# BBB_Headers.net
KiCad netlist of a schematic drawn in Altium Designer
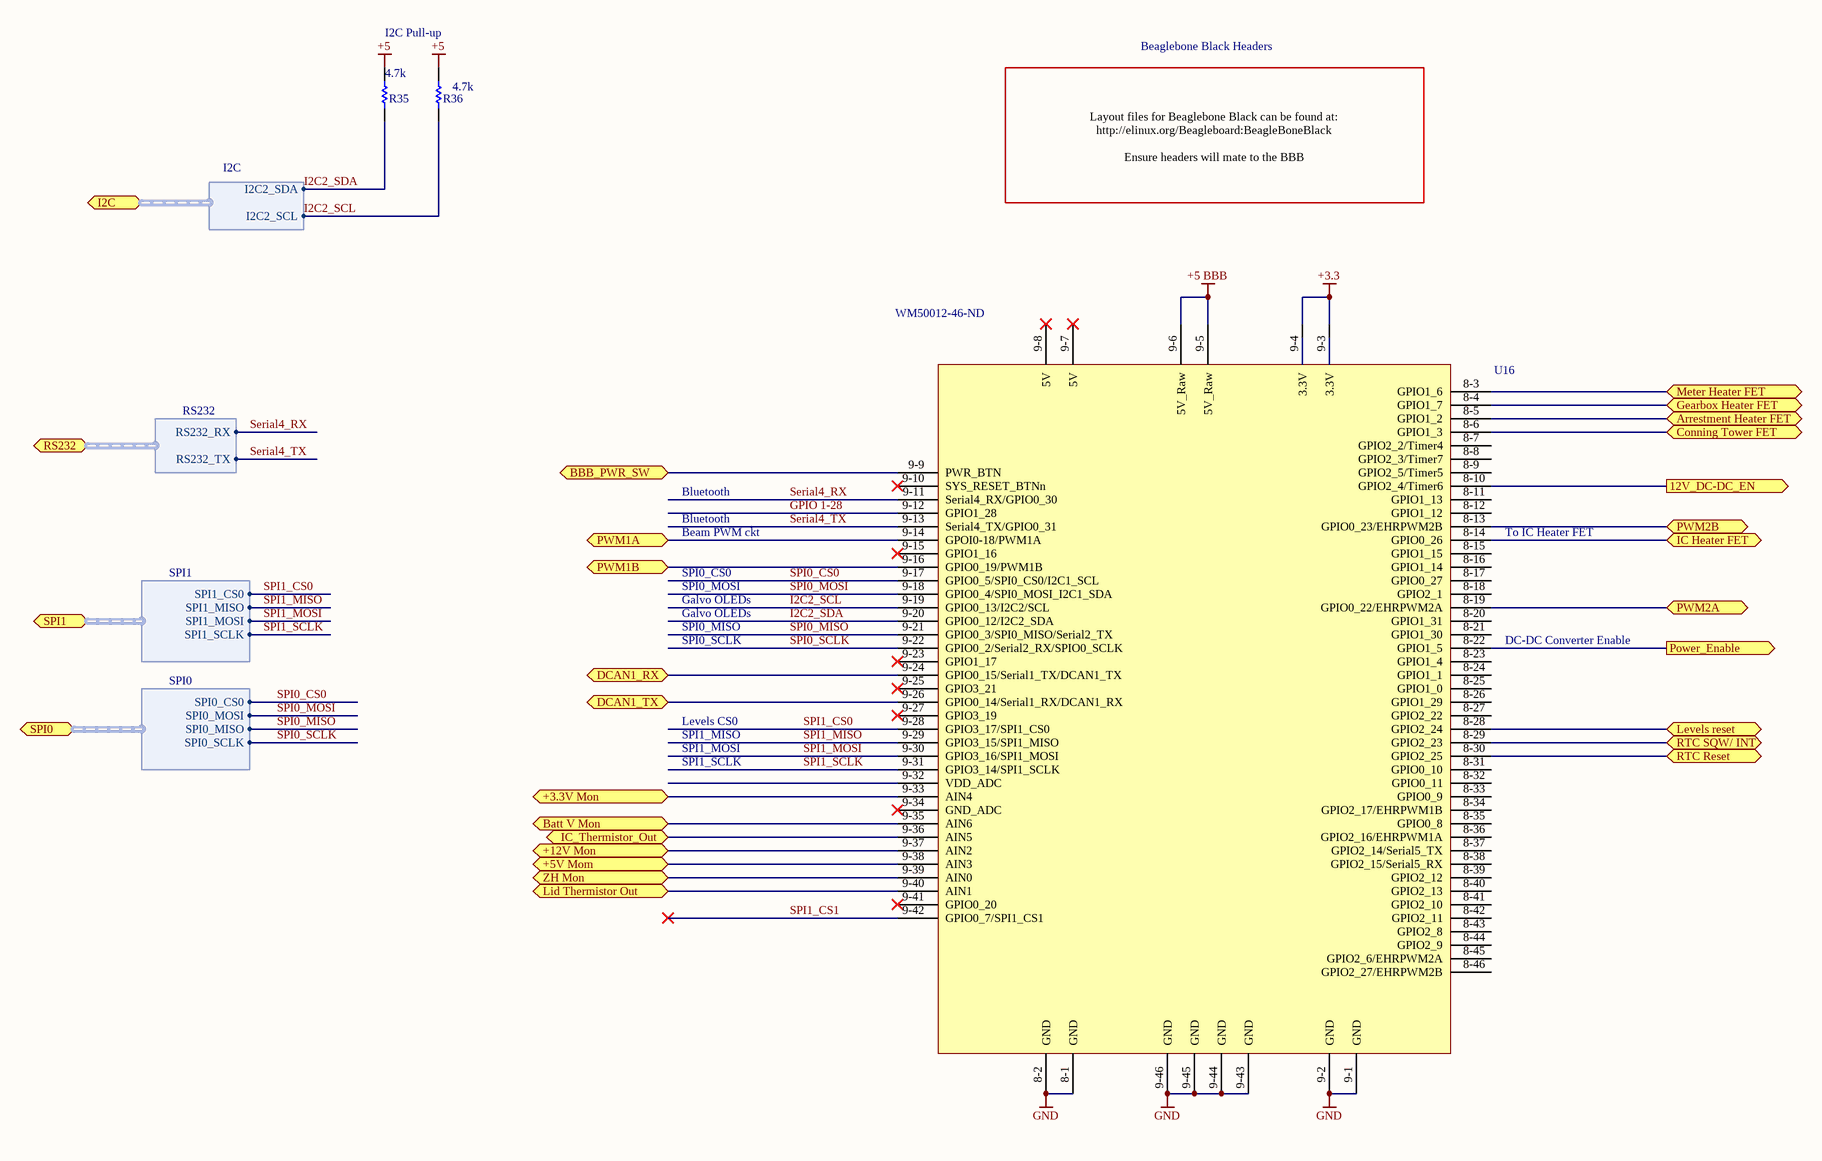
[diagram p0: BBB Headers.SchDoc]

(export (version "E")
  (design (tool "Eeschema 10.0.6"))
  (components
    (comp (ref "R35")
      (value "3K74 0.125W 1% 0805 (2012 Metric)  SMD")
      (footprint "RESC0805(2012)_N")
      (fields
        (field (name "MANUFACTURER") "Vishay Dale")
        (field (name "MANUFACTURER PART NUMBER") "CRCW08054K70FKEA")
        (field (name "RESISTANCE (OHMS)") "4.7k")
        (field (name "TOLERANCE") "±1%")
      )
      (libsource (lib "Altium Content Vault") (part "CMP-1013-00574-1"))
    )
    (comp (ref "R36")
      (value "3K74 0.125W 1% 0805 (2012 Metric)  SMD")
      (footprint "RESC0805(2012)_N")
      (fields
        (field (name "MANUFACTURER") "Vishay Dale")
        (field (name "MANUFACTURER PART NUMBER") "CRCW08054K70FKEA")
        (field (name "RESISTANCE (OHMS)") "4.7k")
        (field (name "TOLERANCE") "±1%")
      )
      (libsource (lib "Altium Content Vault") (part "CMP-1013-00574-1"))
    )
    (comp (ref "U16")
      (value "BBB")
      (footprint "Beaglebone Black")
      (description "Beaglebone Black")
      (fields
        (field (name "SUPPLIER PART NUMBER 1") "WM50012-46-ND")
        (field (name "MANUFACTURER") "Molex, LLC")
        (field (name "MANUFACTURER PART NUMBER") "0010897462")
      )
      (libsource (lib "ZLS_Schematic_lib") (part "Beaglebone_Black"))
    )
  )
  (nets
    (net (code "5") (name "+3.3") (class "Default")
      (node (ref "U16") (pin "9-3") (pinfunction "3.3V_9-3") (pintype "passive"))
      (node (ref "U16") (pin "9-4") (pinfunction "3.3V_9-4") (pintype "passive"))
    )
    (net (code "6") (name "+5") (class "Default")
      (node (ref "R35") (pin "2") (pinfunction "2_2") (pintype "passive"))
      (node (ref "R36") (pin "2") (pinfunction "2_2") (pintype "passive"))
    )
    (net (code "7") (name "+5 BBB") (class "Default")
      (node (ref "U16") (pin "9-5") (pinfunction "5V_Raw_9-5") (pintype "passive"))
      (node (ref "U16") (pin "9-6") (pinfunction "5V_Raw_9-6") (pintype "passive"))
    )
    (net (code "8") (name "/+3.3V Mon") (class "Default")
      (node (ref "U16") (pin "9-33") (pinfunction "AIN4_9-33") (pintype "passive"))
    )
    (net (code "9") (name "/+5V Mom") (class "Default")
      (node (ref "U16") (pin "9-38") (pinfunction "AIN3_9-38") (pintype "passive"))
    )
    (net (code "10") (name "/+12V Mon") (class "Default")
      (node (ref "U16") (pin "9-37") (pinfunction "AIN2_9-37") (pintype "passive"))
    )
    (net (code "11") (name "/12V_DC-DC_EN") (class "Default")
      (node (ref "U16") (pin "8-10") (pinfunction "GPIO2_4/Timer6_8-10") (pintype "passive"))
    )
    (net (code "12") (name "/Arrestment Heater FET") (class "Default")
      (node (ref "U16") (pin "8-5") (pinfunction "GPIO1_2_8-5") (pintype "passive"))
    )
    (net (code "13") (name "/BBB_PWR_SW") (class "Default")
      (node (ref "U16") (pin "9-9") (pinfunction "PWR_BTN_9-9") (pintype "passive"))
    )
    (net (code "14") (name "/Batt V Mon") (class "Default")
      (node (ref "U16") (pin "9-35") (pinfunction "AIN6_9-35") (pintype "passive"))
    )
    (net (code "15") (name "/Conning Tower FET") (class "Default")
      (node (ref "U16") (pin "8-6") (pinfunction "GPIO1_3_8-6") (pintype "passive"))
    )
    (net (code "16") (name "/DCAN1_RX") (class "Default")
      (node (ref "U16") (pin "9-24") (pinfunction "GPIO0_15/Serial1_TX/DCAN1_TX_9-24") (pintype "passive"))
    )
    (net (code "17") (name "/DCAN1_TX") (class "Default")
      (node (ref "U16") (pin "9-26") (pinfunction "GPIO0_14/Serial1_RX/DCAN1_RX_9-26") (pintype "passive"))
    )
    (net (code "18") (name "/GPIO 1-28") (class "Default")
      (node (ref "U16") (pin "9-12") (pinfunction "GPIO1_28_9-12") (pintype "passive"))
    )
    (net (code "19") (name "/Gearbox Heater FET") (class "Default")
      (node (ref "U16") (pin "8-4") (pinfunction "GPIO1_7_8-4") (pintype "passive"))
    )
    (net (code "20") (name "/I2C2_SCL") (class "Default")
      (node (ref "R36") (pin "1") (pinfunction "1_1") (pintype "passive"))
      (node (ref "U16") (pin "9-19") (pinfunction "GPIO0_13/I2C2/SCL_9-19") (pintype "passive"))
    )
    (net (code "21") (name "/I2C2_SDA") (class "Default")
      (node (ref "R35") (pin "1") (pinfunction "1_1") (pintype "passive"))
      (node (ref "U16") (pin "9-20") (pinfunction "GPIO0_12/I2C2_SDA_9-20") (pintype "passive"))
    )
    (net (code "22") (name "/IC Heater FET") (class "Default")
      (node (ref "U16") (pin "8-14") (pinfunction "GPIO0_26_8-14") (pintype "passive"))
    )
    (net (code "23") (name "/IC_Thermistor_Out") (class "Default")
      (node (ref "U16") (pin "9-36") (pinfunction "AIN5_9-36") (pintype "passive"))
    )
    (net (code "24") (name "/Levels reset") (class "Default")
      (node (ref "U16") (pin "8-28") (pinfunction "GPIO2_24_8-28") (pintype "passive"))
    )
    (net (code "25") (name "/Lid Thermistor Out") (class "Default")
      (node (ref "U16") (pin "9-40") (pinfunction "AIN1_9-40") (pintype "passive"))
    )
    (net (code "26") (name "/Meter Heater FET") (class "Default")
      (node (ref "U16") (pin "8-3") (pinfunction "GPIO1_6_8-3") (pintype "passive"))
    )
    (net (code "27") (name "/PWM1A") (class "Default")
      (node (ref "U16") (pin "9-14") (pinfunction "GPOI0-18/PWM1A_9-14") (pintype "passive"))
    )
    (net (code "28") (name "/PWM1B") (class "Default")
      (node (ref "U16") (pin "9-16") (pinfunction "GPIO0_19/PWM1B_9-16") (pintype "passive"))
    )
    (net (code "29") (name "/PWM2A") (class "Default")
      (node (ref "U16") (pin "8-19") (pinfunction "GPIO0_22/EHRPWM2A_8-19") (pintype "passive"))
    )
    (net (code "30") (name "/PWM2B") (class "Default")
      (node (ref "U16") (pin "8-13") (pinfunction "GPIO0_23/EHRPWM2B_8-13") (pintype "passive"))
    )
    (net (code "31") (name "/Power_Enable") (class "Default")
      (node (ref "U16") (pin "8-22") (pinfunction "GPIO1_5_8-22") (pintype "passive"))
    )
    (net (code "32") (name "/RTC Reset") (class "Default")
      (node (ref "U16") (pin "8-30") (pinfunction "GPIO2_25_8-30") (pintype "passive"))
    )
    (net (code "33") (name "/RTC SQW{slash} INT") (class "Default")
      (node (ref "U16") (pin "8-29") (pinfunction "GPIO2_23_8-29") (pintype "passive"))
    )
    (net (code "34") (name "/SPI0_CS0") (class "Default")
      (node (ref "U16") (pin "9-17") (pinfunction "GPIO0_5/SPI0_CS0/I2C1_SCL_9-17") (pintype "passive"))
    )
    (net (code "35") (name "/SPI0_MISO") (class "Default")
      (node (ref "U16") (pin "9-21") (pinfunction "GPIO0_3/SPI0_MISO/Serial2_TX_9-21") (pintype "passive"))
    )
    (net (code "36") (name "/SPI0_MOSI") (class "Default")
      (node (ref "U16") (pin "9-18") (pinfunction "GPIO0_4/SPI0_MOSI_I2C1_SDA_9-18") (pintype "passive"))
    )
    (net (code "37") (name "/SPI0_SCLK") (class "Default")
      (node (ref "U16") (pin "9-22") (pinfunction "GPIO0_2/Serial2_RX/SPIO0_SCLK_9-22") (pintype "passive"))
    )
    (net (code "38") (name "/SPI1_CS0") (class "Default")
      (node (ref "U16") (pin "9-28") (pinfunction "GPIO3_17/SPI1_CS0_9-28") (pintype "passive"))
    )
    (net (code "39") (name "/SPI1_CS1") (class "Default")
      (node (ref "U16") (pin "9-42") (pinfunction "GPIO0_7/SPI1_CS1_9-42") (pintype "passive+no_connect"))
    )
    (net (code "40") (name "/SPI1_MISO") (class "Default")
      (node (ref "U16") (pin "9-29") (pinfunction "GPIO3_15/SPI1_MISO_9-29") (pintype "passive"))
    )
    (net (code "41") (name "/SPI1_MOSI") (class "Default")
      (node (ref "U16") (pin "9-30") (pinfunction "GPIO3_16/SPI1_MOSI_9-30") (pintype "passive"))
    )
    (net (code "42") (name "/SPI1_SCLK") (class "Default")
      (node (ref "U16") (pin "9-31") (pinfunction "GPIO3_14/SPI1_SCLK_9-31") (pintype "passive"))
    )
    (net (code "43") (name "/Serial4_RX") (class "Default")
      (node (ref "U16") (pin "9-11") (pinfunction "Serial4_RX/GPIO0_30_9-11") (pintype "passive"))
    )
    (net (code "44") (name "/Serial4_TX") (class "Default")
      (node (ref "U16") (pin "9-13") (pinfunction "Serial4_TX/GPIO0_31_9-13") (pintype "passive"))
    )
    (net (code "45") (name "/ZH Mon") (class "Default")
      (node (ref "U16") (pin "9-39") (pinfunction "AIN0_9-39") (pintype "passive"))
    )
    (net (code "50") (name "GND") (class "Default")
      (node (ref "U16") (pin "8-1") (pinfunction "GND_8-1") (pintype "passive"))
      (node (ref "U16") (pin "8-2") (pinfunction "GND_8-2") (pintype "passive"))
      (node (ref "U16") (pin "9-1") (pinfunction "GND_9-1") (pintype "passive"))
      (node (ref "U16") (pin "9-2") (pinfunction "GND_9-2") (pintype "passive"))
      (node (ref "U16") (pin "9-43") (pinfunction "GND_9-43") (pintype "passive"))
      (node (ref "U16") (pin "9-44") (pinfunction "GND_9-44") (pintype "passive"))
      (node (ref "U16") (pin "9-45") (pinfunction "GND_9-45") (pintype "passive"))
      (node (ref "U16") (pin "9-46") (pinfunction "GND_9-46") (pintype "passive"))
    )
    (net (code "51") (name "unconnected-(U16-5V-Pad9-7)") (class "Default")
      (node (ref "U16") (pin "9-7") (pinfunction "5V_9-7") (pintype "passive+no_connect"))
    )
    (net (code "52") (name "unconnected-(U16-5V-Pad9-8)") (class "Default")
      (node (ref "U16") (pin "9-8") (pinfunction "5V_9-8") (pintype "passive+no_connect"))
    )
    (net (code "53") (name "unconnected-(U16-GND_ADC-Pad9-34)") (class "Default")
      (node (ref "U16") (pin "9-34") (pinfunction "GND_ADC_9-34") (pintype "passive+no_connect"))
    )
    (net (code "54") (name "unconnected-(U16-GPIO0_8-Pad8-35)") (class "Default")
      (node (ref "U16") (pin "8-35") (pinfunction "GPIO0_8_8-35") (pintype "passive"))
    )
    (net (code "55") (name "unconnected-(U16-GPIO0_9-Pad8-33)") (class "Default")
      (node (ref "U16") (pin "8-33") (pinfunction "GPIO0_9_8-33") (pintype "passive"))
    )
    (net (code "56") (name "unconnected-(U16-GPIO0_10-Pad8-31)") (class "Default")
      (node (ref "U16") (pin "8-31") (pinfunction "GPIO0_10_8-31") (pintype "passive"))
    )
    (net (code "57") (name "unconnected-(U16-GPIO0_11-Pad8-32)") (class "Default")
      (node (ref "U16") (pin "8-32") (pinfunction "GPIO0_11_8-32") (pintype "passive"))
    )
    (net (code "58") (name "unconnected-(U16-GPIO0_20-Pad9-41)") (class "Default")
      (node (ref "U16") (pin "9-41") (pinfunction "GPIO0_20_9-41") (pintype "passive+no_connect"))
    )
    (net (code "59") (name "unconnected-(U16-GPIO0_27-Pad8-17)") (class "Default")
      (node (ref "U16") (pin "8-17") (pinfunction "GPIO0_27_8-17") (pintype "passive"))
    )
    (net (code "60") (name "unconnected-(U16-GPIO1_0-Pad8-25)") (class "Default")
      (node (ref "U16") (pin "8-25") (pinfunction "GPIO1_0_8-25") (pintype "passive"))
    )
    (net (code "61") (name "unconnected-(U16-GPIO1_1-Pad8-24)") (class "Default")
      (node (ref "U16") (pin "8-24") (pinfunction "GPIO1_1_8-24") (pintype "passive"))
    )
    (net (code "62") (name "unconnected-(U16-GPIO1_4-Pad8-23)") (class "Default")
      (node (ref "U16") (pin "8-23") (pinfunction "GPIO1_4_8-23") (pintype "passive"))
    )
    (net (code "63") (name "unconnected-(U16-GPIO1_12-Pad8-12)") (class "Default")
      (node (ref "U16") (pin "8-12") (pinfunction "GPIO1_12_8-12") (pintype "passive"))
    )
    (net (code "64") (name "unconnected-(U16-GPIO1_13-Pad8-11)") (class "Default")
      (node (ref "U16") (pin "8-11") (pinfunction "GPIO1_13_8-11") (pintype "passive"))
    )
    (net (code "65") (name "unconnected-(U16-GPIO1_14-Pad8-16)") (class "Default")
      (node (ref "U16") (pin "8-16") (pinfunction "GPIO1_14_8-16") (pintype "passive"))
    )
    (net (code "66") (name "unconnected-(U16-GPIO1_15-Pad8-15)") (class "Default")
      (node (ref "U16") (pin "8-15") (pinfunction "GPIO1_15_8-15") (pintype "passive"))
    )
    (net (code "67") (name "unconnected-(U16-GPIO1_16-Pad9-15)") (class "Default")
      (node (ref "U16") (pin "9-15") (pinfunction "GPIO1_16_9-15") (pintype "passive+no_connect"))
    )
    (net (code "68") (name "unconnected-(U16-GPIO1_17-Pad9-23)") (class "Default")
      (node (ref "U16") (pin "9-23") (pinfunction "GPIO1_17_9-23") (pintype "passive+no_connect"))
    )
    (net (code "69") (name "unconnected-(U16-GPIO1_29-Pad8-26)") (class "Default")
      (node (ref "U16") (pin "8-26") (pinfunction "GPIO1_29_8-26") (pintype "passive"))
    )
    (net (code "70") (name "unconnected-(U16-GPIO1_30-Pad8-21)") (class "Default")
      (node (ref "U16") (pin "8-21") (pinfunction "GPIO1_30_8-21") (pintype "passive"))
    )
    (net (code "71") (name "unconnected-(U16-GPIO1_31-Pad8-20)") (class "Default")
      (node (ref "U16") (pin "8-20") (pinfunction "GPIO1_31_8-20") (pintype "passive"))
    )
    (net (code "72") (name "unconnected-(U16-GPIO2_1-Pad8-18)") (class "Default")
      (node (ref "U16") (pin "8-18") (pinfunction "GPIO2_1_8-18") (pintype "passive"))
    )
    (net (code "73") (name "unconnected-(U16-GPIO2_2{slash}Timer4-Pad8-7)") (class "Default")
      (node (ref "U16") (pin "8-7") (pinfunction "GPIO2_2/Timer4_8-7") (pintype "passive"))
    )
    (net (code "74") (name "unconnected-(U16-GPIO2_3{slash}Timer7-Pad8-8)") (class "Default")
      (node (ref "U16") (pin "8-8") (pinfunction "GPIO2_3/Timer7_8-8") (pintype "passive"))
    )
    (net (code "75") (name "unconnected-(U16-GPIO2_5{slash}Timer5-Pad8-9)") (class "Default")
      (node (ref "U16") (pin "8-9") (pinfunction "GPIO2_5/Timer5_8-9") (pintype "passive"))
    )
    (net (code "76") (name "unconnected-(U16-GPIO2_6{slash}EHRPWM2A-Pad8-45)") (class "Default")
      (node (ref "U16") (pin "8-45") (pinfunction "GPIO2_6/EHRPWM2A_8-45") (pintype "passive"))
    )
    (net (code "77") (name "unconnected-(U16-GPIO2_8-Pad8-43)") (class "Default")
      (node (ref "U16") (pin "8-43") (pinfunction "GPIO2_8_8-43") (pintype "passive"))
    )
    (net (code "78") (name "unconnected-(U16-GPIO2_9-Pad8-44)") (class "Default")
      (node (ref "U16") (pin "8-44") (pinfunction "GPIO2_9_8-44") (pintype "passive"))
    )
    (net (code "79") (name "unconnected-(U16-GPIO2_10-Pad8-41)") (class "Default")
      (node (ref "U16") (pin "8-41") (pinfunction "GPIO2_10_8-41") (pintype "passive"))
    )
    (net (code "80") (name "unconnected-(U16-GPIO2_11-Pad8-42)") (class "Default")
      (node (ref "U16") (pin "8-42") (pinfunction "GPIO2_11_8-42") (pintype "passive"))
    )
    (net (code "81") (name "unconnected-(U16-GPIO2_12-Pad8-39)") (class "Default")
      (node (ref "U16") (pin "8-39") (pinfunction "GPIO2_12_8-39") (pintype "passive"))
    )
    (net (code "82") (name "unconnected-(U16-GPIO2_13-Pad8-40)") (class "Default")
      (node (ref "U16") (pin "8-40") (pinfunction "GPIO2_13_8-40") (pintype "passive"))
    )
    (net (code "83") (name "unconnected-(U16-GPIO2_14{slash}Serial5_TX-Pad8-37)") (class "Default")
      (node (ref "U16") (pin "8-37") (pinfunction "GPIO2_14/Serial5_TX_8-37") (pintype "passive"))
    )
    (net (code "84") (name "unconnected-(U16-GPIO2_15{slash}Serial5_RX-Pad8-38)") (class "Default")
      (node (ref "U16") (pin "8-38") (pinfunction "GPIO2_15/Serial5_RX_8-38") (pintype "passive"))
    )
    (net (code "85") (name "unconnected-(U16-GPIO2_16{slash}EHRPWM1A-Pad8-36)") (class "Default")
      (node (ref "U16") (pin "8-36") (pinfunction "GPIO2_16/EHRPWM1A_8-36") (pintype "passive"))
    )
    (net (code "86") (name "unconnected-(U16-GPIO2_17{slash}EHRPWM1B-Pad8-34)") (class "Default")
      (node (ref "U16") (pin "8-34") (pinfunction "GPIO2_17/EHRPWM1B_8-34") (pintype "passive"))
    )
    (net (code "87") (name "unconnected-(U16-GPIO2_22-Pad8-27)") (class "Default")
      (node (ref "U16") (pin "8-27") (pinfunction "GPIO2_22_8-27") (pintype "passive"))
    )
    (net (code "88") (name "unconnected-(U16-GPIO2_27{slash}EHRPWM2B-Pad8-46)") (class "Default")
      (node (ref "U16") (pin "8-46") (pinfunction "GPIO2_27/EHRPWM2B_8-46") (pintype "passive"))
    )
    (net (code "89") (name "unconnected-(U16-GPIO3_19-Pad9-27)") (class "Default")
      (node (ref "U16") (pin "9-27") (pinfunction "GPIO3_19_9-27") (pintype "passive+no_connect"))
    )
    (net (code "90") (name "unconnected-(U16-GPIO3_21-Pad9-25)") (class "Default")
      (node (ref "U16") (pin "9-25") (pinfunction "GPIO3_21_9-25") (pintype "passive+no_connect"))
    )
    (net (code "91") (name "unconnected-(U16-SYS_RESET_BTNn-Pad9-10)") (class "Default")
      (node (ref "U16") (pin "9-10") (pinfunction "SYS_RESET_BTNn_9-10") (pintype "passive+no_connect"))
    )
    (net (code "92") (name "unconnected-(U16-VDD_ADC-Pad9-32)") (class "Default")
      (node (ref "U16") (pin "9-32") (pinfunction "VDD_ADC_9-32") (pintype "passive"))
    )
  )
)
